# Display.net
KiCad netlist of a schematic drawn in Altium Designer
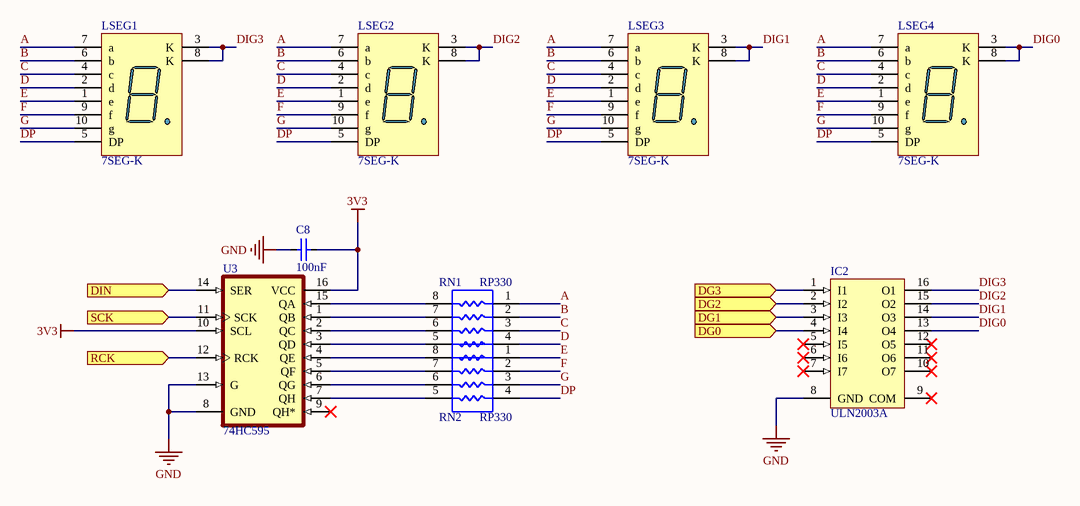
[diagram p0: Display.SchDoc]

(export (version "E")
  (design (tool "Eeschema 10.0.6"))
  (components
    (comp (ref "C8")
      (value "100nF")
      (footprint "CAP_0805")
      (description "Capacitor")
      (fields (field (name "PUBLISHER") "Altium Limited"))
      (libsource (lib "My Library") (part "CapSMD"))
    )
    (comp (ref "IC2")
      (value "ULN2003A")
      (footprint "SOIC16")
      (description "High-Voltage, High-Current Darlington Array")
      (fields (field (name "PUBLISHER") "Altium Limited"))
      (libsource (lib "My Library") (part "ULN2003A"))
    )
    (comp (ref "LSEG1")
      (value "7SEG-K")
      (footprint "LED7SEG")
      (description "14.2 mm General Purpose Blue 7-Segment Display: CC, RH DP, Gray Surface")
      (fields (field (name "PUBLISHER") "Altium Limited"))
      (libsource (lib "My Library") (part "LED7SEG-K"))
    )
    (comp (ref "LSEG2")
      (value "7SEG-K")
      (footprint "LED7SEG")
      (description "14.2 mm General Purpose Blue 7-Segment Display: CC, RH DP, Gray Surface")
      (fields (field (name "PUBLISHER") "Altium Limited"))
      (libsource (lib "My Library") (part "LED7SEG-K"))
    )
    (comp (ref "LSEG3")
      (value "7SEG-K")
      (footprint "LED7SEG")
      (description "14.2 mm General Purpose Blue 7-Segment Display: CC, RH DP, Gray Surface")
      (fields (field (name "PUBLISHER") "Altium Limited"))
      (libsource (lib "My Library") (part "LED7SEG-K"))
    )
    (comp (ref "LSEG4")
      (value "7SEG-K")
      (footprint "LED7SEG")
      (description "14.2 mm General Purpose Blue 7-Segment Display: CC, RH DP, Gray Surface")
      (fields (field (name "PUBLISHER") "Altium Limited"))
      (libsource (lib "My Library") (part "LED7SEG-K"))
    )
    (comp (ref "RN1") (value "RP330") (footprint "RN4-0805") (libsource (lib "My Library") (part "RN4-Dual")))
    (comp (ref "RN2") (value "RP330") (footprint "RN4-0805") (libsource (lib "My Library") (part "RN4-Dual")))
    (comp (ref "U3")
      (value "74HC595")
      (footprint "SOIC16")
      (description "8-bit Serial-Input/Serial or Parallel Output Shift Register with Latched 3-state Outputs")
      (libsource (lib "My Library") (part "74HC595"))
    )
  )
  (nets
    (net (code "1") (name "/A") (class "Default")
      (node (ref "LSEG1") (pin "7") (pinfunction "a_7") (pintype "passive"))
      (node (ref "LSEG2") (pin "7") (pinfunction "a_7") (pintype "passive"))
      (node (ref "LSEG3") (pin "7") (pinfunction "a_7") (pintype "passive"))
      (node (ref "LSEG4") (pin "7") (pinfunction "a_7") (pintype "passive"))
      (node (ref "RN1") (pin "1") (pinfunction "1_1") (pintype "passive"))
    )
    (net (code "2") (name "/B") (class "Default")
      (node (ref "LSEG1") (pin "6") (pinfunction "b_6") (pintype "passive"))
      (node (ref "LSEG2") (pin "6") (pinfunction "b_6") (pintype "passive"))
      (node (ref "LSEG3") (pin "6") (pinfunction "b_6") (pintype "passive"))
      (node (ref "LSEG4") (pin "6") (pinfunction "b_6") (pintype "passive"))
      (node (ref "RN1") (pin "2") (pinfunction "2_2") (pintype "passive"))
    )
    (net (code "3") (name "/C") (class "Default")
      (node (ref "LSEG1") (pin "4") (pinfunction "c_4") (pintype "passive"))
      (node (ref "LSEG2") (pin "4") (pinfunction "c_4") (pintype "passive"))
      (node (ref "LSEG3") (pin "4") (pinfunction "c_4") (pintype "passive"))
      (node (ref "LSEG4") (pin "4") (pinfunction "c_4") (pintype "passive"))
      (node (ref "RN1") (pin "3") (pinfunction "3_3") (pintype "passive"))
    )
    (net (code "4") (name "/D") (class "Default")
      (node (ref "LSEG1") (pin "2") (pinfunction "d_2") (pintype "passive"))
      (node (ref "LSEG2") (pin "2") (pinfunction "d_2") (pintype "passive"))
      (node (ref "LSEG3") (pin "2") (pinfunction "d_2") (pintype "passive"))
      (node (ref "LSEG4") (pin "2") (pinfunction "d_2") (pintype "passive"))
      (node (ref "RN1") (pin "4") (pinfunction "4_4") (pintype "passive"))
    )
    (net (code "5") (name "/DG0") (class "Default")
      (node (ref "IC2") (pin "4") (pinfunction "I4_4") (pintype "input"))
    )
    (net (code "6") (name "/DG1") (class "Default")
      (node (ref "IC2") (pin "3") (pinfunction "I3_3") (pintype "input"))
    )
    (net (code "7") (name "/DG2") (class "Default")
      (node (ref "IC2") (pin "2") (pinfunction "I2_2") (pintype "input"))
    )
    (net (code "8") (name "/DG3") (class "Default")
      (node (ref "IC2") (pin "1") (pinfunction "I1_1") (pintype "input"))
    )
    (net (code "9") (name "/DIG0") (class "Default")
      (node (ref "IC2") (pin "13") (pinfunction "O4_13") (pintype "open_collector"))
      (node (ref "LSEG4") (pin "3") (pinfunction "K_3") (pintype "passive"))
      (node (ref "LSEG4") (pin "8") (pinfunction "K_8") (pintype "passive"))
    )
    (net (code "10") (name "/DIG1") (class "Default")
      (node (ref "IC2") (pin "14") (pinfunction "O3_14") (pintype "open_collector"))
      (node (ref "LSEG3") (pin "3") (pinfunction "K_3") (pintype "passive"))
      (node (ref "LSEG3") (pin "8") (pinfunction "K_8") (pintype "passive"))
    )
    (net (code "11") (name "/DIG2") (class "Default")
      (node (ref "IC2") (pin "15") (pinfunction "O2_15") (pintype "open_collector"))
      (node (ref "LSEG2") (pin "3") (pinfunction "K_3") (pintype "passive"))
      (node (ref "LSEG2") (pin "8") (pinfunction "K_8") (pintype "passive"))
    )
    (net (code "12") (name "/DIG3") (class "Default")
      (node (ref "IC2") (pin "16") (pinfunction "O1_16") (pintype "open_collector"))
      (node (ref "LSEG1") (pin "3") (pinfunction "K_3") (pintype "passive"))
      (node (ref "LSEG1") (pin "8") (pinfunction "K_8") (pintype "passive"))
    )
    (net (code "13") (name "/DIN") (class "Default")
      (node (ref "U3") (pin "14") (pinfunction "SER_14") (pintype "input"))
    )
    (net (code "14") (name "/DP") (class "Default")
      (node (ref "LSEG1") (pin "5") (pinfunction "DP_5") (pintype "passive"))
      (node (ref "LSEG2") (pin "5") (pinfunction "DP_5") (pintype "passive"))
      (node (ref "LSEG3") (pin "5") (pinfunction "DP_5") (pintype "passive"))
      (node (ref "LSEG4") (pin "5") (pinfunction "DP_5") (pintype "passive"))
      (node (ref "RN2") (pin "4") (pinfunction "4_4") (pintype "passive"))
    )
    (net (code "15") (name "/E") (class "Default")
      (node (ref "LSEG1") (pin "1") (pinfunction "e_1") (pintype "passive"))
      (node (ref "LSEG2") (pin "1") (pinfunction "e_1") (pintype "passive"))
      (node (ref "LSEG3") (pin "1") (pinfunction "e_1") (pintype "passive"))
      (node (ref "LSEG4") (pin "1") (pinfunction "e_1") (pintype "passive"))
      (node (ref "RN2") (pin "1") (pinfunction "1_1") (pintype "passive"))
    )
    (net (code "16") (name "/F") (class "Default")
      (node (ref "LSEG1") (pin "9") (pinfunction "f_9") (pintype "passive"))
      (node (ref "LSEG2") (pin "9") (pinfunction "f_9") (pintype "passive"))
      (node (ref "LSEG3") (pin "9") (pinfunction "f_9") (pintype "passive"))
      (node (ref "LSEG4") (pin "9") (pinfunction "f_9") (pintype "passive"))
      (node (ref "RN2") (pin "2") (pinfunction "2_2") (pintype "passive"))
    )
    (net (code "17") (name "/G") (class "Default")
      (node (ref "LSEG1") (pin "10") (pinfunction "g_10") (pintype "passive"))
      (node (ref "LSEG2") (pin "10") (pinfunction "g_10") (pintype "passive"))
      (node (ref "LSEG3") (pin "10") (pinfunction "g_10") (pintype "passive"))
      (node (ref "LSEG4") (pin "10") (pinfunction "g_10") (pintype "passive"))
      (node (ref "RN2") (pin "3") (pinfunction "3_3") (pintype "passive"))
    )
    (net (code "18") (name "/RCK") (class "Default")
      (node (ref "U3") (pin "12") (pinfunction "RCK_12") (pintype "input"))
    )
    (net (code "19") (name "/SCK") (class "Default")
      (node (ref "U3") (pin "11") (pinfunction "SCK_11") (pintype "input"))
    )
    (net (code "20") (name "3V3") (class "Default")
      (node (ref "C8") (pin "1") (pinfunction "1_1") (pintype "passive"))
      (node (ref "U3") (pin "10") (pinfunction "SCL_10") (pintype "input"))
      (node (ref "U3") (pin "16") (pinfunction "VCC_16") (pintype "power_in"))
    )
    (net (code "21") (name "GND") (class "Default")
      (node (ref "C8") (pin "2") (pinfunction "2_2") (pintype "passive"))
      (node (ref "IC2") (pin "8") (pinfunction "GND_8") (pintype "power_in"))
      (node (ref "U3") (pin "13") (pinfunction "G_13") (pintype "input"))
      (node (ref "U3") (pin "8") (pinfunction "GND_8") (pintype "power_in"))
    )
    (net (code "22") (name "Net-(U3-QA)") (class "Default")
      (node (ref "RN1") (pin "8") (pinfunction "8_8") (pintype "passive"))
      (node (ref "U3") (pin "15") (pinfunction "QA_15") (pintype "input"))
    )
    (net (code "23") (name "Net-(U3-QB)") (class "Default")
      (node (ref "RN1") (pin "7") (pinfunction "7_7") (pintype "passive"))
      (node (ref "U3") (pin "1") (pinfunction "QB_1") (pintype "input"))
    )
    (net (code "24") (name "Net-(U3-QC)") (class "Default")
      (node (ref "RN1") (pin "6") (pinfunction "6_6") (pintype "passive"))
      (node (ref "U3") (pin "2") (pinfunction "QC_2") (pintype "input"))
    )
    (net (code "25") (name "Net-(U3-QD)") (class "Default")
      (node (ref "RN1") (pin "5") (pinfunction "5_5") (pintype "passive"))
      (node (ref "U3") (pin "3") (pinfunction "QD_3") (pintype "input"))
    )
    (net (code "26") (name "Net-(U3-QE)") (class "Default")
      (node (ref "RN2") (pin "8") (pinfunction "8_8") (pintype "passive"))
      (node (ref "U3") (pin "4") (pinfunction "QE_4") (pintype "input"))
    )
    (net (code "27") (name "Net-(U3-QF)") (class "Default")
      (node (ref "RN2") (pin "7") (pinfunction "7_7") (pintype "passive"))
      (node (ref "U3") (pin "5") (pinfunction "QF_5") (pintype "input"))
    )
    (net (code "28") (name "Net-(U3-QG)") (class "Default")
      (node (ref "RN2") (pin "6") (pinfunction "6_6") (pintype "passive"))
      (node (ref "U3") (pin "6") (pinfunction "QG_6") (pintype "input"))
    )
    (net (code "29") (name "Net-(U3-QH)") (class "Default")
      (node (ref "RN2") (pin "5") (pinfunction "5_5") (pintype "passive"))
      (node (ref "U3") (pin "7") (pinfunction "QH_7") (pintype "input"))
    )
    (net (code "30") (name "unconnected-(IC2-COM-Pad9)") (class "Default")
      (node (ref "IC2") (pin "9") (pinfunction "COM_9") (pintype "passive+no_connect"))
    )
    (net (code "31") (name "unconnected-(IC2-I5-Pad5)") (class "Default")
      (node (ref "IC2") (pin "5") (pinfunction "I5_5") (pintype "input+no_connect"))
    )
    (net (code "32") (name "unconnected-(IC2-I6-Pad6)") (class "Default")
      (node (ref "IC2") (pin "6") (pinfunction "I6_6") (pintype "input+no_connect"))
    )
    (net (code "33") (name "unconnected-(IC2-I7-Pad7)") (class "Default")
      (node (ref "IC2") (pin "7") (pinfunction "I7_7") (pintype "input+no_connect"))
    )
    (net (code "34") (name "unconnected-(IC2-O5-Pad12)") (class "Default")
      (node (ref "IC2") (pin "12") (pinfunction "O5_12") (pintype "open_collector+no_connect"))
    )
    (net (code "35") (name "unconnected-(IC2-O6-Pad11)") (class "Default")
      (node (ref "IC2") (pin "11") (pinfunction "O6_11") (pintype "open_collector+no_connect"))
    )
    (net (code "36") (name "unconnected-(IC2-O7-Pad10)") (class "Default")
      (node (ref "IC2") (pin "10") (pinfunction "O7_10") (pintype "open_collector+no_connect"))
    )
    (net (code "37") (name "unconnected-(U3-QH*-Pad9)") (class "Default")
      (node (ref "U3") (pin "9") (pinfunction "QH*_9") (pintype "input+no_connect"))
    )
  )
)
